# Input.net
KiCad netlist of a schematic drawn in Altium Designer
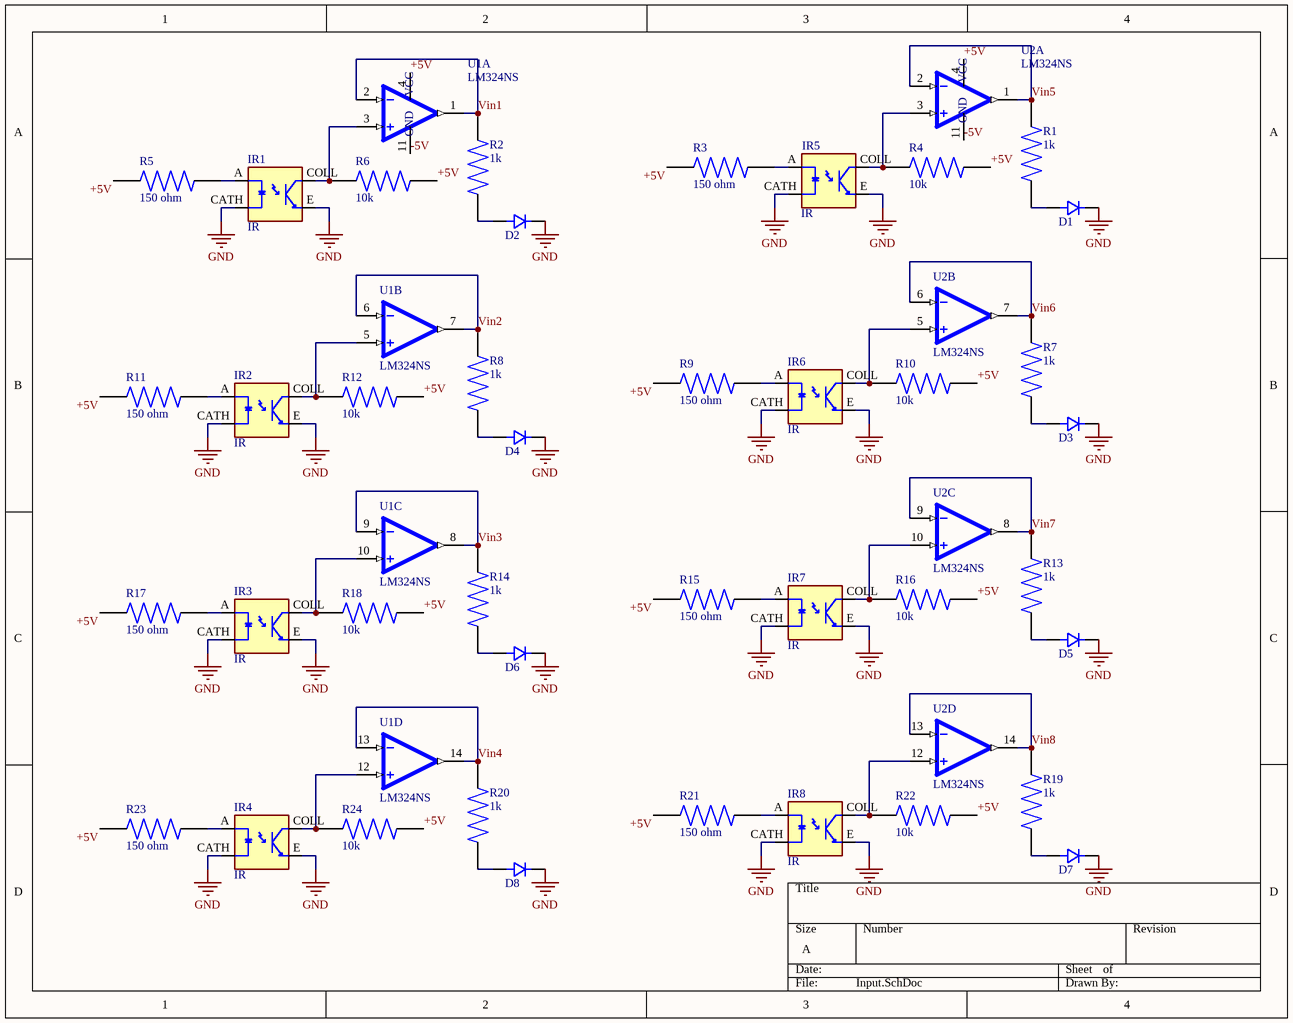
[diagram p0: Input.SchDoc]

(export (version "E")
  (design (tool "Eeschema 10.0.6"))
  (components
    (comp (ref "D1")
      (value "150080RS75000")
      (footprint "150080RS75000")
      (libsource (lib "Integrated_Library_analog_project") (part "150080RS75000"))
    )
    (comp (ref "D2")
      (value "150080RS75000")
      (footprint "150080RS75000")
      (libsource (lib "Integrated_Library_analog_project") (part "150080RS75000"))
    )
    (comp (ref "D3")
      (value "150080RS75000")
      (footprint "150080RS75000")
      (libsource (lib "Integrated_Library_analog_project") (part "150080RS75000"))
    )
    (comp (ref "D4")
      (value "150080RS75000")
      (footprint "150080RS75000")
      (libsource (lib "Integrated_Library_analog_project") (part "150080RS75000"))
    )
    (comp (ref "D5")
      (value "150080RS75000")
      (footprint "150080RS75000")
      (libsource (lib "Integrated_Library_analog_project") (part "150080RS75000"))
    )
    (comp (ref "D6")
      (value "150080RS75000")
      (footprint "150080RS75000")
      (libsource (lib "Integrated_Library_analog_project") (part "150080RS75000"))
    )
    (comp (ref "D7")
      (value "150080RS75000")
      (footprint "150080RS75000")
      (libsource (lib "Integrated_Library_analog_project") (part "150080RS75000"))
    )
    (comp (ref "D8")
      (value "150080RS75000")
      (footprint "150080RS75000")
      (libsource (lib "Integrated_Library_analog_project") (part "150080RS75000"))
    )
    (comp (ref "IR1")
      (value "IR")
      (footprint "OPTO_TCRT5000")
      (description "950 nm 60 mA Through Hole Reflective Optical Sensor with Transistor Output; TCRT5000")
      (fields (field (name "MP") "TCRT5000"))
      (libsource (lib "irs") (part "IR"))
    )
    (comp (ref "IR2")
      (value "IR")
      (footprint "OPTO_TCRT5000")
      (description "950 nm 60 mA Through Hole Reflective Optical Sensor with Transistor Output; TCRT5000")
      (fields (field (name "MP") "TCRT5000"))
      (libsource (lib "irs") (part "IR"))
    )
    (comp (ref "IR3")
      (value "IR")
      (footprint "OPTO_TCRT5000")
      (description "950 nm 60 mA Through Hole Reflective Optical Sensor with Transistor Output; TCRT5000")
      (fields (field (name "MP") "TCRT5000"))
      (libsource (lib "irs") (part "IR"))
    )
    (comp (ref "IR4")
      (value "IR")
      (footprint "OPTO_TCRT5000")
      (description "950 nm 60 mA Through Hole Reflective Optical Sensor with Transistor Output; TCRT5000")
      (fields (field (name "MP") "TCRT5000"))
      (libsource (lib "irs") (part "IR"))
    )
    (comp (ref "IR5")
      (value "IR")
      (footprint "OPTO_TCRT5000")
      (description "950 nm 60 mA Through Hole Reflective Optical Sensor with Transistor Output; TCRT5000")
      (fields (field (name "MP") "TCRT5000"))
      (libsource (lib "irs") (part "IR"))
    )
    (comp (ref "IR6")
      (value "IR")
      (footprint "OPTO_TCRT5000")
      (description "950 nm 60 mA Through Hole Reflective Optical Sensor with Transistor Output; TCRT5000")
      (fields (field (name "MP") "TCRT5000"))
      (libsource (lib "irs") (part "IR"))
    )
    (comp (ref "IR7")
      (value "IR")
      (footprint "OPTO_TCRT5000")
      (description "950 nm 60 mA Through Hole Reflective Optical Sensor with Transistor Output; TCRT5000")
      (fields (field (name "MP") "TCRT5000"))
      (libsource (lib "irs") (part "IR"))
    )
    (comp (ref "IR8")
      (value "IR")
      (footprint "OPTO_TCRT5000")
      (description "950 nm 60 mA Through Hole Reflective Optical Sensor with Transistor Output; TCRT5000")
      (fields (field (name "MP") "TCRT5000"))
      (libsource (lib "irs") (part "IR"))
    )
    (comp (ref "R1")
      (value "1k")
      (footprint "RESC2012X60N")
      (fields
        (field (name "DIGIKEY_PART_NUMBER") "311-1.00KCRTR-ND")
        (field (name "MF") "Yageo")
        (field (name "MP") "RC0805FR-071KL")
      )
      (libsource (lib "1ks") (part "1k"))
    )
    (comp (ref "R2")
      (value "1k")
      (footprint "RESC2012X60N")
      (fields
        (field (name "DIGIKEY_PART_NUMBER") "311-1.00KCRTR-ND")
        (field (name "MF") "Yageo")
        (field (name "MP") "RC0805FR-071KL")
      )
      (libsource (lib "1ks") (part "1k"))
    )
    (comp (ref "R3")
      (value "150 ohm")
      (footprint "RESC2012X60N")
      (fields (field (name "MF") "Yageo") (field (name "MP") "RC0805FR-07150RL"))
      (libsource (lib "150 ohm") (part "150 ohm"))
    )
    (comp (ref "R4")
      (value "10k")
      (footprint "RESC2012X60N")
      (fields (field (name "MF") "Yageo") (field (name "MP") "RC0805FR-0710KL"))
      (libsource (lib "10ks") (part "10k"))
    )
    (comp (ref "R5")
      (value "150 ohm")
      (footprint "RESC2012X60N")
      (fields (field (name "MF") "Yageo") (field (name "MP") "RC0805FR-07150RL"))
      (libsource (lib "150 ohm") (part "150 ohm"))
    )
    (comp (ref "R6")
      (value "10k")
      (footprint "RESC2012X60N")
      (fields (field (name "MF") "Yageo") (field (name "MP") "RC0805FR-0710KL"))
      (libsource (lib "10ks") (part "10k"))
    )
    (comp (ref "R7")
      (value "1k")
      (footprint "RESC2012X60N")
      (fields
        (field (name "DIGIKEY_PART_NUMBER") "311-1.00KCRTR-ND")
        (field (name "MF") "Yageo")
        (field (name "MP") "RC0805FR-071KL")
      )
      (libsource (lib "1ks") (part "1k"))
    )
    (comp (ref "R8")
      (value "1k")
      (footprint "RESC2012X60N")
      (fields
        (field (name "DIGIKEY_PART_NUMBER") "311-1.00KCRTR-ND")
        (field (name "MF") "Yageo")
        (field (name "MP") "RC0805FR-071KL")
      )
      (libsource (lib "1ks") (part "1k"))
    )
    (comp (ref "R9")
      (value "150 ohm")
      (footprint "RESC2012X60N")
      (fields (field (name "MF") "Yageo") (field (name "MP") "RC0805FR-07150RL"))
      (libsource (lib "150 ohm") (part "150 ohm"))
    )
    (comp (ref "R10")
      (value "10k")
      (footprint "RESC2012X60N")
      (fields (field (name "MF") "Yageo") (field (name "MP") "RC0805FR-0710KL"))
      (libsource (lib "10ks") (part "10k"))
    )
    (comp (ref "R11")
      (value "150 ohm")
      (footprint "RESC2012X60N")
      (fields (field (name "MF") "Yageo") (field (name "MP") "RC0805FR-07150RL"))
      (libsource (lib "150 ohm") (part "150 ohm"))
    )
    (comp (ref "R12")
      (value "10k")
      (footprint "RESC2012X60N")
      (fields (field (name "MF") "Yageo") (field (name "MP") "RC0805FR-0710KL"))
      (libsource (lib "10ks") (part "10k"))
    )
    (comp (ref "R13")
      (value "1k")
      (footprint "RESC2012X60N")
      (fields
        (field (name "DIGIKEY_PART_NUMBER") "311-1.00KCRTR-ND")
        (field (name "MF") "Yageo")
        (field (name "MP") "RC0805FR-071KL")
      )
      (libsource (lib "1ks") (part "1k"))
    )
    (comp (ref "R14")
      (value "1k")
      (footprint "RESC2012X60N")
      (fields
        (field (name "DIGIKEY_PART_NUMBER") "311-1.00KCRTR-ND")
        (field (name "MF") "Yageo")
        (field (name "MP") "RC0805FR-071KL")
      )
      (libsource (lib "1ks") (part "1k"))
    )
    (comp (ref "R15")
      (value "150 ohm")
      (footprint "RESC2012X60N")
      (fields (field (name "MF") "Yageo") (field (name "MP") "RC0805FR-07150RL"))
      (libsource (lib "150 ohm") (part "150 ohm"))
    )
    (comp (ref "R16")
      (value "10k")
      (footprint "RESC2012X60N")
      (fields (field (name "MF") "Yageo") (field (name "MP") "RC0805FR-0710KL"))
      (libsource (lib "10ks") (part "10k"))
    )
    (comp (ref "R17")
      (value "150 ohm")
      (footprint "RESC2012X60N")
      (fields (field (name "MF") "Yageo") (field (name "MP") "RC0805FR-07150RL"))
      (libsource (lib "150 ohm") (part "150 ohm"))
    )
    (comp (ref "R18")
      (value "10k")
      (footprint "RESC2012X60N")
      (fields (field (name "MF") "Yageo") (field (name "MP") "RC0805FR-0710KL"))
      (libsource (lib "10ks") (part "10k"))
    )
    (comp (ref "R19")
      (value "1k")
      (footprint "RESC2012X60N")
      (fields
        (field (name "DIGIKEY_PART_NUMBER") "311-1.00KCRTR-ND")
        (field (name "MF") "Yageo")
        (field (name "MP") "RC0805FR-071KL")
      )
      (libsource (lib "1ks") (part "1k"))
    )
    (comp (ref "R20")
      (value "1k")
      (footprint "RESC2012X60N")
      (fields
        (field (name "DIGIKEY_PART_NUMBER") "311-1.00KCRTR-ND")
        (field (name "MF") "Yageo")
        (field (name "MP") "RC0805FR-071KL")
      )
      (libsource (lib "1ks") (part "1k"))
    )
    (comp (ref "R21")
      (value "150 ohm")
      (footprint "RESC2012X60N")
      (fields (field (name "MF") "Yageo") (field (name "MP") "RC0805FR-07150RL"))
      (libsource (lib "150 ohm") (part "150 ohm"))
    )
    (comp (ref "R22")
      (value "10k")
      (footprint "RESC2012X60N")
      (fields (field (name "MF") "Yageo") (field (name "MP") "RC0805FR-0710KL"))
      (libsource (lib "10ks") (part "10k"))
    )
    (comp (ref "R23")
      (value "150 ohm")
      (footprint "RESC2012X60N")
      (fields (field (name "MF") "Yageo") (field (name "MP") "RC0805FR-07150RL"))
      (libsource (lib "150 ohm") (part "150 ohm"))
    )
    (comp (ref "R24")
      (value "10k")
      (footprint "RESC2012X60N")
      (fields (field (name "MF") "Yageo") (field (name "MP") "RC0805FR-0710KL"))
      (libsource (lib "10ks") (part "10k"))
    )
    (comp (ref "U1")
      (value "LM324NS")
      (footprint "SOIC127P780X200-14N")
      (description "4-Channel industry standard operational amplifier 14-SO 0 to 70; LM324NSRG4")
      (fields (field (name "MP") "LM324NSRG4") (field (name "MF") "Texas Instruments"))
      (libsource (lib "LM324NSRG4") (part "LM324NS"))
    )
    (comp (ref "U2")
      (value "LM324NS")
      (footprint "SOIC127P780X200-14N")
      (description "4-Channel industry standard operational amplifier 14-SO 0 to 70; LM324NSRG4")
      (fields (field (name "MP") "LM324NSRG4") (field (name "MF") "Texas Instruments"))
      (libsource (lib "LM324NSRG4") (part "LM324NS"))
    )
  )
  (nets
    (net (code "1") (name "/+5V") (class "Default")
      (node (ref "R10") (pin "2") (pinfunction "2_2") (pintype "passive"))
      (node (ref "R11") (pin "1") (pinfunction "1_1") (pintype "passive"))
      (node (ref "R12") (pin "2") (pinfunction "2_2") (pintype "passive"))
      (node (ref "R15") (pin "1") (pinfunction "1_1") (pintype "passive"))
      (node (ref "R16") (pin "2") (pinfunction "2_2") (pintype "passive"))
      (node (ref "R17") (pin "1") (pinfunction "1_1") (pintype "passive"))
      (node (ref "R18") (pin "2") (pinfunction "2_2") (pintype "passive"))
      (node (ref "R21") (pin "1") (pinfunction "1_1") (pintype "passive"))
      (node (ref "R22") (pin "2") (pinfunction "2_2") (pintype "passive"))
      (node (ref "R23") (pin "1") (pinfunction "1_1") (pintype "passive"))
      (node (ref "R24") (pin "2") (pinfunction "2_2") (pintype "passive"))
      (node (ref "R3") (pin "1") (pinfunction "1_1") (pintype "passive"))
      (node (ref "R4") (pin "2") (pinfunction "2_2") (pintype "passive"))
      (node (ref "R5") (pin "1") (pinfunction "1_1") (pintype "passive"))
      (node (ref "R6") (pin "2") (pinfunction "2_2") (pintype "passive"))
      (node (ref "R9") (pin "1") (pinfunction "1_1") (pintype "passive"))
      (node (ref "U1") (pin "4") (pinfunction "VCC_4") (pintype "power_in"))
      (node (ref "U2") (pin "4") (pinfunction "VCC_4") (pintype "power_in"))
    )
    (net (code "2") (name "/-5V") (class "Default")
      (node (ref "U1") (pin "11") (pinfunction "GND_11") (pintype "power_in"))
      (node (ref "U2") (pin "11") (pinfunction "GND_11") (pintype "power_in"))
    )
    (net (code "3") (name "/Vin1") (class "Default")
      (node (ref "R2") (pin "2") (pinfunction "2_2") (pintype "passive"))
      (node (ref "U1") (pin "1") (pinfunction "1OUT_1") (pintype "output"))
      (node (ref "U1") (pin "2") (pinfunction "1IN-_2") (pintype "input"))
    )
    (net (code "4") (name "/Vin2") (class "Default")
      (node (ref "R8") (pin "2") (pinfunction "2_2") (pintype "passive"))
      (node (ref "U1") (pin "6") (pinfunction "2IN-_6") (pintype "input"))
      (node (ref "U1") (pin "7") (pinfunction "2OUT_7") (pintype "output"))
    )
    (net (code "5") (name "/Vin3") (class "Default")
      (node (ref "R14") (pin "2") (pinfunction "2_2") (pintype "passive"))
      (node (ref "U1") (pin "8") (pinfunction "3OUT_8") (pintype "output"))
      (node (ref "U1") (pin "9") (pinfunction "3IN-_9") (pintype "input"))
    )
    (net (code "6") (name "/Vin4") (class "Default")
      (node (ref "R20") (pin "2") (pinfunction "2_2") (pintype "passive"))
      (node (ref "U1") (pin "13") (pinfunction "4IN-_13") (pintype "input"))
      (node (ref "U1") (pin "14") (pinfunction "4OUT_14") (pintype "output"))
    )
    (net (code "7") (name "/Vin5") (class "Default")
      (node (ref "R1") (pin "2") (pinfunction "2_2") (pintype "passive"))
      (node (ref "U2") (pin "1") (pinfunction "1OUT_1") (pintype "output"))
      (node (ref "U2") (pin "2") (pinfunction "1IN-_2") (pintype "input"))
    )
    (net (code "8") (name "/Vin6") (class "Default")
      (node (ref "R7") (pin "2") (pinfunction "2_2") (pintype "passive"))
      (node (ref "U2") (pin "6") (pinfunction "2IN-_6") (pintype "input"))
      (node (ref "U2") (pin "7") (pinfunction "2OUT_7") (pintype "output"))
    )
    (net (code "9") (name "/Vin7") (class "Default")
      (node (ref "R13") (pin "2") (pinfunction "2_2") (pintype "passive"))
      (node (ref "U2") (pin "8") (pinfunction "3OUT_8") (pintype "output"))
      (node (ref "U2") (pin "9") (pinfunction "3IN-_9") (pintype "input"))
    )
    (net (code "10") (name "/Vin8") (class "Default")
      (node (ref "R19") (pin "2") (pinfunction "2_2") (pintype "passive"))
      (node (ref "U2") (pin "13") (pinfunction "4IN-_13") (pintype "input"))
      (node (ref "U2") (pin "14") (pinfunction "4OUT_14") (pintype "output"))
    )
    (net (code "11") (name "GND") (class "Default")
      (node (ref "D1") (pin "2") (pinfunction "2_2") (pintype "passive"))
      (node (ref "D2") (pin "2") (pinfunction "2_2") (pintype "passive"))
      (node (ref "D3") (pin "2") (pinfunction "2_2") (pintype "passive"))
      (node (ref "D4") (pin "2") (pinfunction "2_2") (pintype "passive"))
      (node (ref "D5") (pin "2") (pinfunction "2_2") (pintype "passive"))
      (node (ref "D6") (pin "2") (pinfunction "2_2") (pintype "passive"))
      (node (ref "D7") (pin "2") (pinfunction "2_2") (pintype "passive"))
      (node (ref "D8") (pin "2") (pinfunction "2_2") (pintype "passive"))
      (node (ref "IR1") (pin "CATH") (pinfunction "CATH_CATH") (pintype "passive"))
      (node (ref "IR1") (pin "E") (pinfunction "E_E") (pintype "passive"))
      (node (ref "IR2") (pin "CATH") (pinfunction "CATH_CATH") (pintype "passive"))
      (node (ref "IR2") (pin "E") (pinfunction "E_E") (pintype "passive"))
      (node (ref "IR3") (pin "CATH") (pinfunction "CATH_CATH") (pintype "passive"))
      (node (ref "IR3") (pin "E") (pinfunction "E_E") (pintype "passive"))
      (node (ref "IR4") (pin "CATH") (pinfunction "CATH_CATH") (pintype "passive"))
      (node (ref "IR4") (pin "E") (pinfunction "E_E") (pintype "passive"))
      (node (ref "IR5") (pin "CATH") (pinfunction "CATH_CATH") (pintype "passive"))
      (node (ref "IR5") (pin "E") (pinfunction "E_E") (pintype "passive"))
      (node (ref "IR6") (pin "CATH") (pinfunction "CATH_CATH") (pintype "passive"))
      (node (ref "IR6") (pin "E") (pinfunction "E_E") (pintype "passive"))
      (node (ref "IR7") (pin "CATH") (pinfunction "CATH_CATH") (pintype "passive"))
      (node (ref "IR7") (pin "E") (pinfunction "E_E") (pintype "passive"))
      (node (ref "IR8") (pin "CATH") (pinfunction "CATH_CATH") (pintype "passive"))
      (node (ref "IR8") (pin "E") (pinfunction "E_E") (pintype "passive"))
    )
    (net (code "12") (name "Net-(D1-Pad1)") (class "Default")
      (node (ref "D1") (pin "1") (pinfunction "1_1") (pintype "passive"))
      (node (ref "R1") (pin "1") (pinfunction "1_1") (pintype "passive"))
    )
    (net (code "13") (name "Net-(D2-Pad1)") (class "Default")
      (node (ref "D2") (pin "1") (pinfunction "1_1") (pintype "passive"))
      (node (ref "R2") (pin "1") (pinfunction "1_1") (pintype "passive"))
    )
    (net (code "14") (name "Net-(D3-Pad1)") (class "Default")
      (node (ref "D3") (pin "1") (pinfunction "1_1") (pintype "passive"))
      (node (ref "R7") (pin "1") (pinfunction "1_1") (pintype "passive"))
    )
    (net (code "15") (name "Net-(D4-Pad1)") (class "Default")
      (node (ref "D4") (pin "1") (pinfunction "1_1") (pintype "passive"))
      (node (ref "R8") (pin "1") (pinfunction "1_1") (pintype "passive"))
    )
    (net (code "16") (name "Net-(D5-Pad1)") (class "Default")
      (node (ref "D5") (pin "1") (pinfunction "1_1") (pintype "passive"))
      (node (ref "R13") (pin "1") (pinfunction "1_1") (pintype "passive"))
    )
    (net (code "17") (name "Net-(D6-Pad1)") (class "Default")
      (node (ref "D6") (pin "1") (pinfunction "1_1") (pintype "passive"))
      (node (ref "R14") (pin "1") (pinfunction "1_1") (pintype "passive"))
    )
    (net (code "18") (name "Net-(D7-Pad1)") (class "Default")
      (node (ref "D7") (pin "1") (pinfunction "1_1") (pintype "passive"))
      (node (ref "R19") (pin "1") (pinfunction "1_1") (pintype "passive"))
    )
    (net (code "19") (name "Net-(D8-Pad1)") (class "Default")
      (node (ref "D8") (pin "1") (pinfunction "1_1") (pintype "passive"))
      (node (ref "R20") (pin "1") (pinfunction "1_1") (pintype "passive"))
    )
    (net (code "20") (name "Net-(IR1-PadA)") (class "Default")
      (node (ref "IR1") (pin "A") (pinfunction "A_A") (pintype "passive"))
      (node (ref "R5") (pin "2") (pinfunction "2_2") (pintype "passive"))
    )
    (net (code "21") (name "Net-(IR2-PadA)") (class "Default")
      (node (ref "IR2") (pin "A") (pinfunction "A_A") (pintype "passive"))
      (node (ref "R11") (pin "2") (pinfunction "2_2") (pintype "passive"))
    )
    (net (code "22") (name "Net-(IR3-PadA)") (class "Default")
      (node (ref "IR3") (pin "A") (pinfunction "A_A") (pintype "passive"))
      (node (ref "R17") (pin "2") (pinfunction "2_2") (pintype "passive"))
    )
    (net (code "23") (name "Net-(IR4-PadA)") (class "Default")
      (node (ref "IR4") (pin "A") (pinfunction "A_A") (pintype "passive"))
      (node (ref "R23") (pin "2") (pinfunction "2_2") (pintype "passive"))
    )
    (net (code "24") (name "Net-(IR5-PadA)") (class "Default")
      (node (ref "IR5") (pin "A") (pinfunction "A_A") (pintype "passive"))
      (node (ref "R3") (pin "2") (pinfunction "2_2") (pintype "passive"))
    )
    (net (code "25") (name "Net-(IR6-PadA)") (class "Default")
      (node (ref "IR6") (pin "A") (pinfunction "A_A") (pintype "passive"))
      (node (ref "R9") (pin "2") (pinfunction "2_2") (pintype "passive"))
    )
    (net (code "26") (name "Net-(IR7-PadA)") (class "Default")
      (node (ref "IR7") (pin "A") (pinfunction "A_A") (pintype "passive"))
      (node (ref "R15") (pin "2") (pinfunction "2_2") (pintype "passive"))
    )
    (net (code "27") (name "Net-(IR8-PadA)") (class "Default")
      (node (ref "IR8") (pin "A") (pinfunction "A_A") (pintype "passive"))
      (node (ref "R21") (pin "2") (pinfunction "2_2") (pintype "passive"))
    )
    (net (code "28") (name "Net-(U1A-1IN+)") (class "Default")
      (node (ref "IR1") (pin "COLL") (pinfunction "COLL_COLL") (pintype "passive"))
      (node (ref "R6") (pin "1") (pinfunction "1_1") (pintype "passive"))
      (node (ref "U1") (pin "3") (pinfunction "1IN+_3") (pintype "input"))
    )
    (net (code "29") (name "Net-(U1B-2IN+)") (class "Default")
      (node (ref "IR2") (pin "COLL") (pinfunction "COLL_COLL") (pintype "passive"))
      (node (ref "R12") (pin "1") (pinfunction "1_1") (pintype "passive"))
      (node (ref "U1") (pin "5") (pinfunction "2IN+_5") (pintype "input"))
    )
    (net (code "30") (name "Net-(U1C-3IN+)") (class "Default")
      (node (ref "IR3") (pin "COLL") (pinfunction "COLL_COLL") (pintype "passive"))
      (node (ref "R18") (pin "1") (pinfunction "1_1") (pintype "passive"))
      (node (ref "U1") (pin "10") (pinfunction "3IN+_10") (pintype "input"))
    )
    (net (code "31") (name "Net-(U1D-4IN+)") (class "Default")
      (node (ref "IR4") (pin "COLL") (pinfunction "COLL_COLL") (pintype "passive"))
      (node (ref "R24") (pin "1") (pinfunction "1_1") (pintype "passive"))
      (node (ref "U1") (pin "12") (pinfunction "4IN+_12") (pintype "input"))
    )
    (net (code "32") (name "Net-(U2A-1IN+)") (class "Default")
      (node (ref "IR5") (pin "COLL") (pinfunction "COLL_COLL") (pintype "passive"))
      (node (ref "R4") (pin "1") (pinfunction "1_1") (pintype "passive"))
      (node (ref "U2") (pin "3") (pinfunction "1IN+_3") (pintype "input"))
    )
    (net (code "33") (name "Net-(U2B-2IN+)") (class "Default")
      (node (ref "IR6") (pin "COLL") (pinfunction "COLL_COLL") (pintype "passive"))
      (node (ref "R10") (pin "1") (pinfunction "1_1") (pintype "passive"))
      (node (ref "U2") (pin "5") (pinfunction "2IN+_5") (pintype "input"))
    )
    (net (code "34") (name "Net-(U2C-3IN+)") (class "Default")
      (node (ref "IR7") (pin "COLL") (pinfunction "COLL_COLL") (pintype "passive"))
      (node (ref "R16") (pin "1") (pinfunction "1_1") (pintype "passive"))
      (node (ref "U2") (pin "10") (pinfunction "3IN+_10") (pintype "input"))
    )
    (net (code "35") (name "Net-(U2D-4IN+)") (class "Default")
      (node (ref "IR8") (pin "COLL") (pinfunction "COLL_COLL") (pintype "passive"))
      (node (ref "R22") (pin "1") (pinfunction "1_1") (pintype "passive"))
      (node (ref "U2") (pin "12") (pinfunction "4IN+_12") (pintype "input"))
    )
  )
)
